# HL_gas_o3_pcb.net
KiCad netlist of a schematic drawn in EAGLE
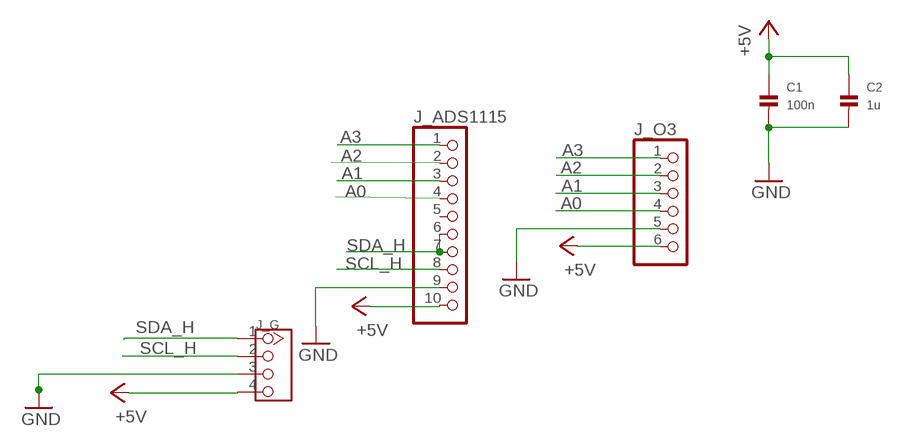
[diagram p0: schematic, sheet 1]

(export (version "E")
  (design (tool "Eeschema 10.0.6"))
  (components
    (comp (ref "C1")
      (value "100n")
      (footprint "eagle-import:1206")
      (libsource (lib "eagle-import") (part "CAP_CERAMIC1206"))
    )
    (comp (ref "C2")
      (value "1u")
      (footprint "eagle-import:1206")
      (libsource (lib "eagle-import") (part "CAP_CERAMIC1206"))
    )
    (comp (ref "J_ADS1115")
      (value "HEADER-1X10")
      (footprint "eagle-import:1X10_OVAL")
      (libsource (lib "eagle-import") (part "HEADER-1X10"))
    )
    (comp (ref "J_G")
      (value "TWIG-4P-2.0-2.0")
      (footprint "eagle-import:4P-2.0")
      (libsource (lib "eagle-import") (part "TWIG-4P-2.0-2.0"))
    )
    (comp (ref "J_O3")
      (value "HEADER-1X6")
      (footprint "eagle-import:1X06_OVAL")
      (libsource (lib "eagle-import") (part "HEADER-1X6"))
    )
  )
  (nets
    (net (code "1") (name "+5V") (class "Default")
      (node (ref "C1") (pin "1") (pinfunction "P$1_1") (pintype "passive"))
      (node (ref "C2") (pin "1") (pinfunction "P$1_1") (pintype "passive"))
      (node (ref "J_ADS1115") (pin "10") (pinfunction "10_10") (pintype "passive"))
      (node (ref "J_G") (pin "4") (pinfunction "4_4") (pintype "bidirectional"))
      (node (ref "J_O3") (pin "6") (pinfunction "6_6") (pintype "passive"))
    )
    (net (code "2") (name "/A0") (class "Default")
      (node (ref "J_ADS1115") (pin "4") (pinfunction "4_4") (pintype "passive"))
      (node (ref "J_O3") (pin "4") (pinfunction "4_4") (pintype "passive"))
    )
    (net (code "3") (name "/A1") (class "Default")
      (node (ref "J_ADS1115") (pin "3") (pinfunction "3_3") (pintype "passive"))
      (node (ref "J_O3") (pin "3") (pinfunction "3_3") (pintype "passive"))
    )
    (net (code "4") (name "/A2") (class "Default")
      (node (ref "J_ADS1115") (pin "2") (pinfunction "2_2") (pintype "passive"))
      (node (ref "J_O3") (pin "2") (pinfunction "2_2") (pintype "passive"))
    )
    (net (code "5") (name "/A3") (class "Default")
      (node (ref "J_ADS1115") (pin "1") (pinfunction "1_1") (pintype "passive"))
      (node (ref "J_O3") (pin "1") (pinfunction "1_1") (pintype "passive"))
    )
    (net (code "6") (name "/SCL_H") (class "Default")
      (node (ref "J_ADS1115") (pin "8") (pinfunction "8_8") (pintype "passive"))
      (node (ref "J_G") (pin "2") (pinfunction "2_2") (pintype "bidirectional"))
    )
    (net (code "7") (name "/SDA_H") (class "Default")
      (node (ref "J_ADS1115") (pin "6") (pinfunction "6_6") (pintype "passive"))
      (node (ref "J_ADS1115") (pin "7") (pinfunction "7_7") (pintype "passive"))
      (node (ref "J_G") (pin "1") (pinfunction "1_1") (pintype "bidirectional"))
    )
    (net (code "8") (name "GND") (class "Default")
      (node (ref "C1") (pin "2") (pinfunction "P$2_2") (pintype "passive"))
      (node (ref "C2") (pin "2") (pinfunction "P$2_2") (pintype "passive"))
      (node (ref "J_ADS1115") (pin "9") (pinfunction "9_9") (pintype "passive"))
      (node (ref "J_G") (pin "3") (pinfunction "3_3") (pintype "bidirectional"))
      (node (ref "J_O3") (pin "5") (pinfunction "5_5") (pintype "passive"))
    )
    (net (code "9") (name "unconnected-(J_ADS1115-Pad5)") (class "Default")
      (node (ref "J_ADS1115") (pin "5") (pinfunction "5_5") (pintype "passive"))
    )
  )
)
